# Analog_Input_Reased_and_Protection_Circu.net
KiCad netlist of a schematic drawn in EAGLE
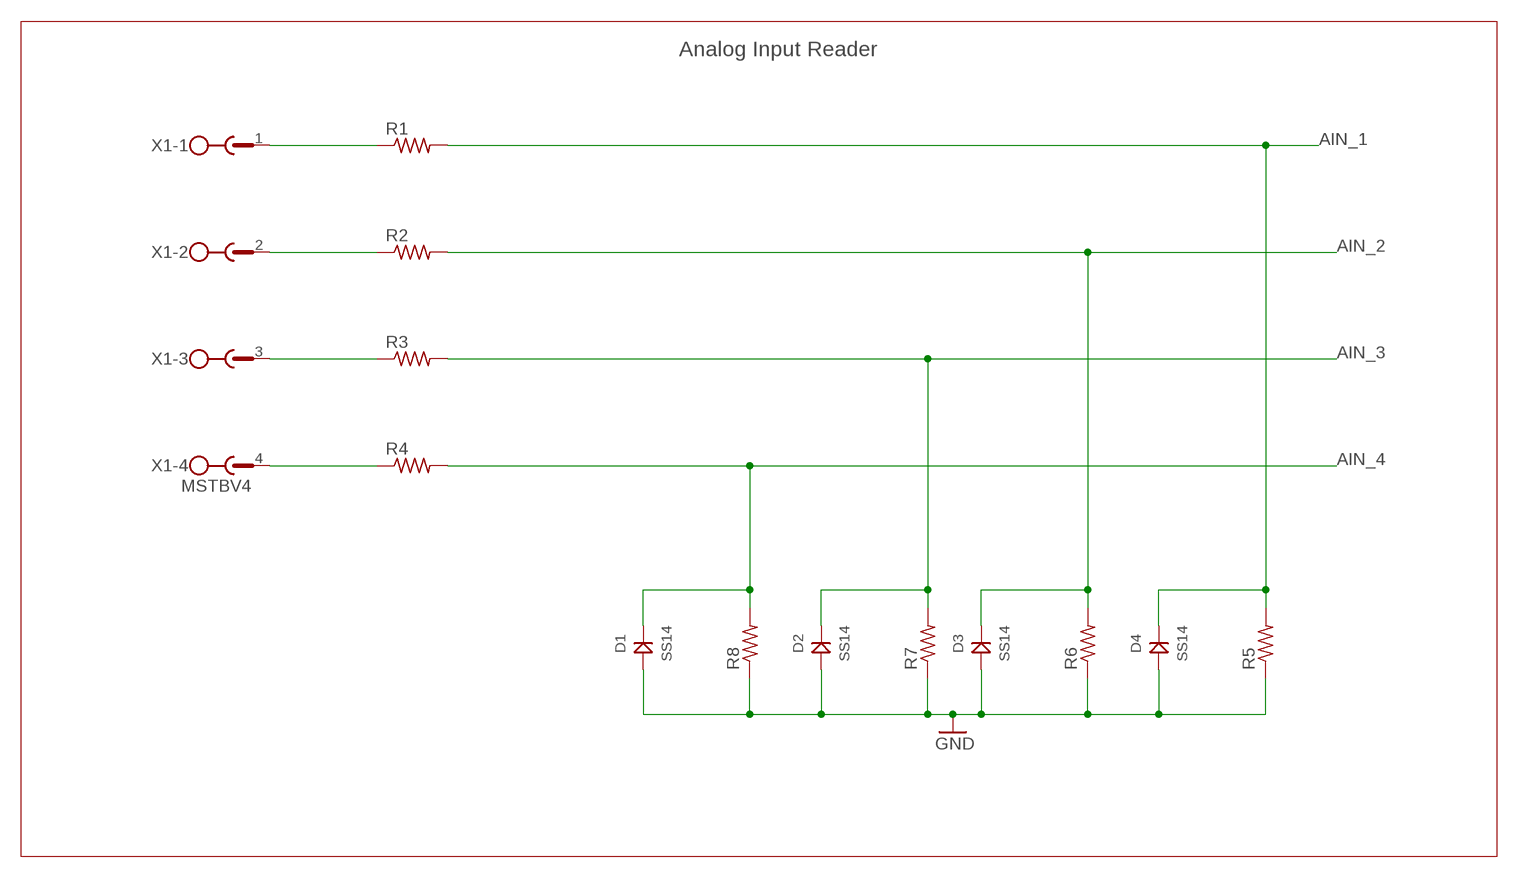
[diagram p0: schematic, sheet 1]

(export (version "E")
  (design (tool "Eeschema 10.0.6"))
  (components
    (comp (ref "D1")
      (value "SS14")
      (footprint "eagle-import:DO214")
      (fields (field (name "MF") "ON Semiconductor"))
      (libsource (lib "eagle-import") (part "SS14"))
    )
    (comp (ref "D2")
      (value "SS14")
      (footprint "eagle-import:DO214")
      (fields (field (name "MF") "ON Semiconductor"))
      (libsource (lib "eagle-import") (part "SS14"))
    )
    (comp (ref "D3")
      (value "SS14")
      (footprint "eagle-import:DO214")
      (fields (field (name "MF") "ON Semiconductor"))
      (libsource (lib "eagle-import") (part "SS14"))
    )
    (comp (ref "D4")
      (value "SS14")
      (footprint "eagle-import:DO214")
      (fields (field (name "MF") "ON Semiconductor"))
      (libsource (lib "eagle-import") (part "SS14"))
    )
    (comp (ref "R1")
      (value "R-US_R0805")
      (footprint "eagle-import:R0805")
      (libsource (lib "eagle-import") (part "R-US_R0805"))
    )
    (comp (ref "R2")
      (value "R-US_R0805")
      (footprint "eagle-import:R0805")
      (libsource (lib "eagle-import") (part "R-US_R0805"))
    )
    (comp (ref "R3")
      (value "R-US_R0805")
      (footprint "eagle-import:R0805")
      (libsource (lib "eagle-import") (part "R-US_R0805"))
    )
    (comp (ref "R4")
      (value "R-US_R0805")
      (footprint "eagle-import:R0805")
      (libsource (lib "eagle-import") (part "R-US_R0805"))
    )
    (comp (ref "R5")
      (value "R-US_R0805")
      (footprint "eagle-import:R0805")
      (libsource (lib "eagle-import") (part "R-US_R0805"))
    )
    (comp (ref "R6")
      (value "R-US_R0805")
      (footprint "eagle-import:R0805")
      (libsource (lib "eagle-import") (part "R-US_R0805"))
    )
    (comp (ref "R7")
      (value "R-US_R0805")
      (footprint "eagle-import:R0805")
      (libsource (lib "eagle-import") (part "R-US_R0805"))
    )
    (comp (ref "R8")
      (value "R-US_R0805")
      (footprint "eagle-import:R0805")
      (libsource (lib "eagle-import") (part "R-US_R0805"))
    )
    (comp (ref "X1")
      (value "MSTBV4")
      (footprint "eagle-import:MSTBV4")
      (fields (field (name "MPN") "MSTBV 2,5/4-GF-5.08"))
      (libsource (lib "eagle-import") (part "MSTBV4"))
    )
  )
  (nets
    (net (code "1") (name "/AIN_1") (class "Default")
      (node (ref "D4") (pin "CATHODE") (pinfunction "KATHODE_CATHODE") (pintype "bidirectional"))
      (node (ref "R1") (pin "2") (pinfunction "2_2") (pintype "passive"))
      (node (ref "R5") (pin "2") (pinfunction "2_2") (pintype "passive"))
    )
    (net (code "2") (name "/AIN_2") (class "Default")
      (node (ref "D3") (pin "CATHODE") (pinfunction "KATHODE_CATHODE") (pintype "bidirectional"))
      (node (ref "R2") (pin "2") (pinfunction "2_2") (pintype "passive"))
      (node (ref "R6") (pin "2") (pinfunction "2_2") (pintype "passive"))
    )
    (net (code "3") (name "/AIN_3") (class "Default")
      (node (ref "D2") (pin "CATHODE") (pinfunction "KATHODE_CATHODE") (pintype "bidirectional"))
      (node (ref "R3") (pin "2") (pinfunction "2_2") (pintype "passive"))
      (node (ref "R7") (pin "2") (pinfunction "2_2") (pintype "passive"))
    )
    (net (code "4") (name "/AIN_4") (class "Default")
      (node (ref "D1") (pin "CATHODE") (pinfunction "KATHODE_CATHODE") (pintype "bidirectional"))
      (node (ref "R4") (pin "2") (pinfunction "2_2") (pintype "passive"))
      (node (ref "R8") (pin "2") (pinfunction "2_2") (pintype "passive"))
    )
    (net (code "5") (name "GND") (class "Default")
      (node (ref "D1") (pin "ANODE") (pinfunction "ANODE_ANODE") (pintype "bidirectional"))
      (node (ref "D2") (pin "ANODE") (pinfunction "ANODE_ANODE") (pintype "bidirectional"))
      (node (ref "D3") (pin "ANODE") (pinfunction "ANODE_ANODE") (pintype "bidirectional"))
      (node (ref "D4") (pin "ANODE") (pinfunction "ANODE_ANODE") (pintype "bidirectional"))
      (node (ref "R5") (pin "1") (pinfunction "1_1") (pintype "passive"))
      (node (ref "R6") (pin "1") (pinfunction "1_1") (pintype "passive"))
      (node (ref "R7") (pin "1") (pinfunction "1_1") (pintype "passive"))
      (node (ref "R8") (pin "1") (pinfunction "1_1") (pintype "passive"))
    )
    (net (code "6") (name "Net-(R1-Pad1)") (class "Default")
      (node (ref "R1") (pin "1") (pinfunction "1_1") (pintype "passive"))
      (node (ref "X1") (pin "1") (pinfunction "1_1") (pintype "passive"))
    )
    (net (code "7") (name "Net-(X1B-1)") (class "Default")
      (node (ref "R2") (pin "1") (pinfunction "1_1") (pintype "passive"))
      (node (ref "X1") (pin "2") (pinfunction "1_2") (pintype "passive"))
    )
    (net (code "8") (name "Net-(X1C-1)") (class "Default")
      (node (ref "R3") (pin "1") (pinfunction "1_1") (pintype "passive"))
      (node (ref "X1") (pin "3") (pinfunction "1_3") (pintype "passive"))
    )
    (net (code "9") (name "Net-(X1D-1)") (class "Default")
      (node (ref "R4") (pin "1") (pinfunction "1_1") (pintype "passive"))
      (node (ref "X1") (pin "4") (pinfunction "1_4") (pintype "passive"))
    )
  )
)
